# MAZ000168_-_Diagrama_el_ctrico.net
KiCad netlist of a schematic drawn in Altium Designer
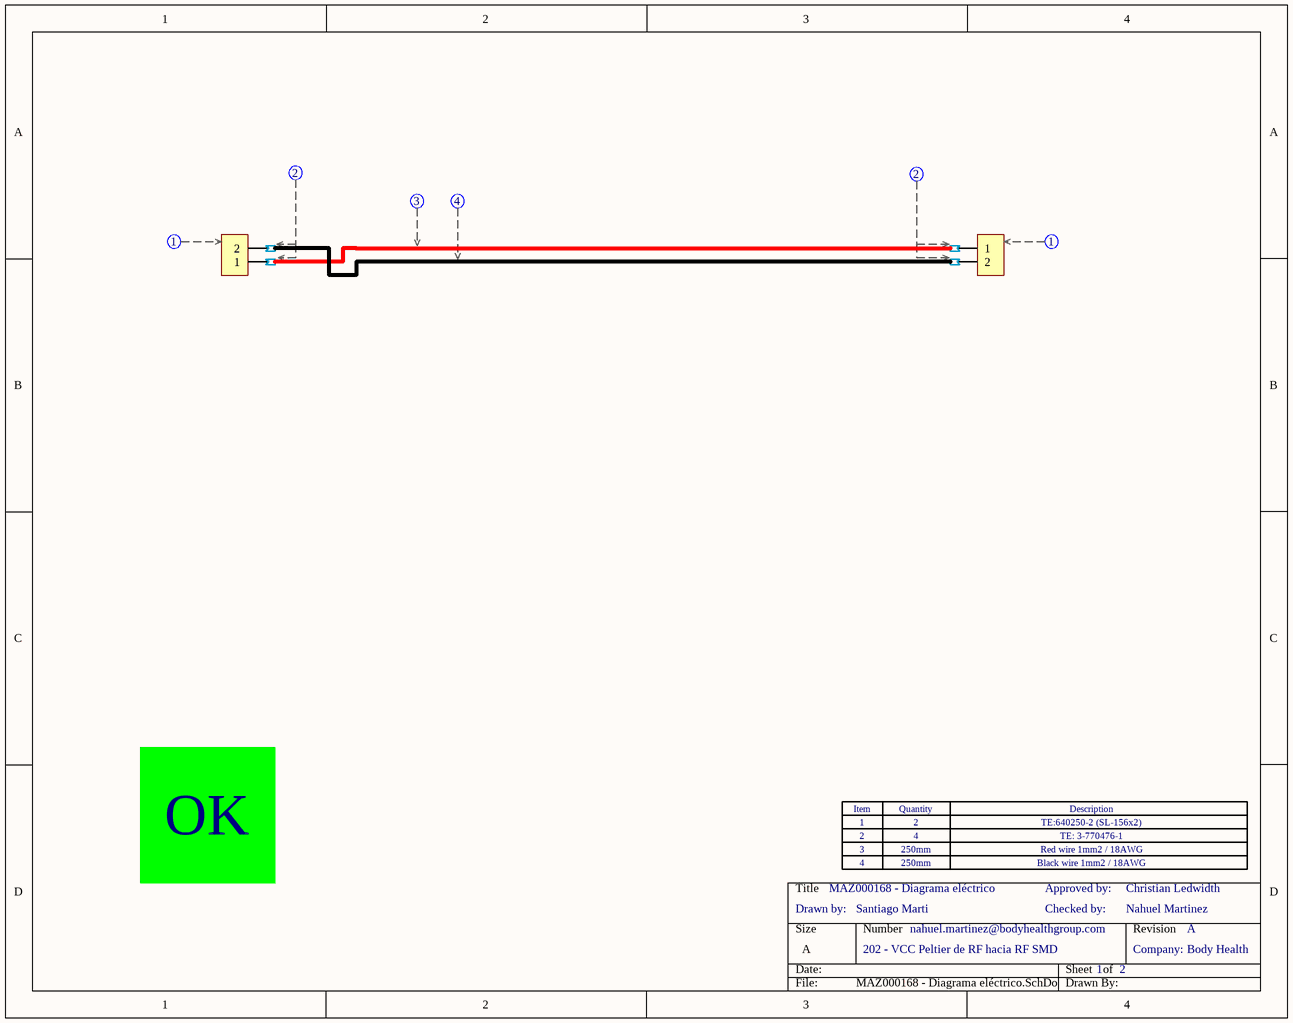
[diagram p0: MAZ000168 - Diagrama eléctrico.SchDoc]

(export (version "E")
  (design (tool "Eeschema 10.0.6"))
  (components
    (comp (ref "Con1")
      (value "SL156-2")
      (description "CONN RECEPT 2 POS W/RAMP SL-156")
      (libsource (lib "LibreriaParaPlanos") (part "SL156-2"))
    )
    (comp (ref "Con2")
      (value "SL156-2")
      (description "CONN RECEPT 2 POS W/RAMP SL-156")
      (libsource (lib "") (part "SL156-2_1"))
    )
    (comp (ref "Soc1")
      (value "sock_SL156_770476-1")
      (description "CONN SOCKET 18-24AWG CRIMP TIN")
      (libsource (lib "LibreriaParaPlanos") (part "sock_SL156_770476-1"))
    )
    (comp (ref "Soc2")
      (value "sock_SL156_770476-1")
      (description "CONN SOCKET 18-24AWG CRIMP TIN")
      (libsource (lib "LibreriaParaPlanos") (part "sock_SL156_770476-1"))
    )
    (comp (ref "Soc3")
      (value "sock_SL156_770476-1")
      (description "CONN SOCKET 18-24AWG CRIMP TIN")
      (libsource (lib "LibreriaParaPlanos") (part "sock_SL156_770476-1"))
    )
    (comp (ref "Soc4")
      (value "sock_SL156_770476-1")
      (description "CONN SOCKET 18-24AWG CRIMP TIN")
      (libsource (lib "LibreriaParaPlanos") (part "sock_SL156_770476-1"))
    )
    (comp (ref "Soc5")
      (value "sock_SL156_770476-1")
      (description "CONN SOCKET 18-24AWG CRIMP TIN")
      (libsource (lib "LibreriaParaPlanos") (part "sock_SL156_770476-1"))
    )
    (comp (ref "Zoc1")
      (value "Zócalo_Header")
      (description "Header para el zócalo de referencias")
      (libsource (lib "LibreriaParaPlanos") (part "Zócalo_Header"))
    )
    (comp (ref "Zoc2")
      (value "Zócalo_Item")
      (description "Ítem para el zócalo de referencias")
      (libsource (lib "LibreriaParaPlanos") (part "Zócalo_Item"))
    )
    (comp (ref "Zoc3")
      (value "Zócalo_Item")
      (description "Ítem para el zócalo de referencias")
      (libsource (lib "LibreriaParaPlanos") (part "Zócalo_Item"))
    )
    (comp (ref "Zoc4")
      (value "Zócalo_Item")
      (description "Ítem para el zócalo de referencias")
      (libsource (lib "LibreriaParaPlanos") (part "Zócalo_Item"))
    )
    (comp (ref "Zoc5")
      (value "Zócalo_Item")
      (description "Ítem para el zócalo de referencias")
      (libsource (lib "LibreriaParaPlanos") (part "Zócalo_Item"))
    )
  )
  (nets
    (net (code "1") (name "Net-(Con1-Pad1)") (class "Default")
      (node (ref "Con1") (pin "1") (pinfunction "1_1") (pintype "passive"))
      (node (ref "Soc3") (pin "0") (pinfunction "0_0") (pintype "passive"))
    )
    (net (code "2") (name "Net-(Con1-Pad2)") (class "Default")
      (node (ref "Con1") (pin "2") (pinfunction "2_2") (pintype "passive"))
      (node (ref "Soc1") (pin "0") (pinfunction "0_0") (pintype "passive"))
    )
    (net (code "3") (name "Net-(Con2-Pad1)") (class "Default")
      (node (ref "Con2") (pin "1") (pinfunction "1_1") (pintype "passive"))
      (node (ref "Soc2") (pin "0") (pinfunction "0_0") (pintype "passive"))
    )
    (net (code "4") (name "Net-(Con2-Pad2)") (class "Default")
      (node (ref "Con2") (pin "2") (pinfunction "2_2") (pintype "passive"))
      (node (ref "Soc4") (pin "0") (pinfunction "0_0") (pintype "passive"))
    )
    (net (code "5") (name "Net-(Soc1-Pad1)") (class "Default")
      (node (ref "Soc1") (pin "1") (pinfunction "1_1") (pintype "passive"))
      (node (ref "Soc4") (pin "1") (pinfunction "1_1") (pintype "passive"))
    )
    (net (code "6") (name "Net-(Soc2-Pad1)") (class "Default")
      (node (ref "Soc2") (pin "1") (pinfunction "1_1") (pintype "passive"))
      (node (ref "Soc3") (pin "1") (pinfunction "1_1") (pintype "passive"))
    )
  )
)
